# AdapterDIP8M16.net
KiCad netlist of a schematic drawn in EAGLE
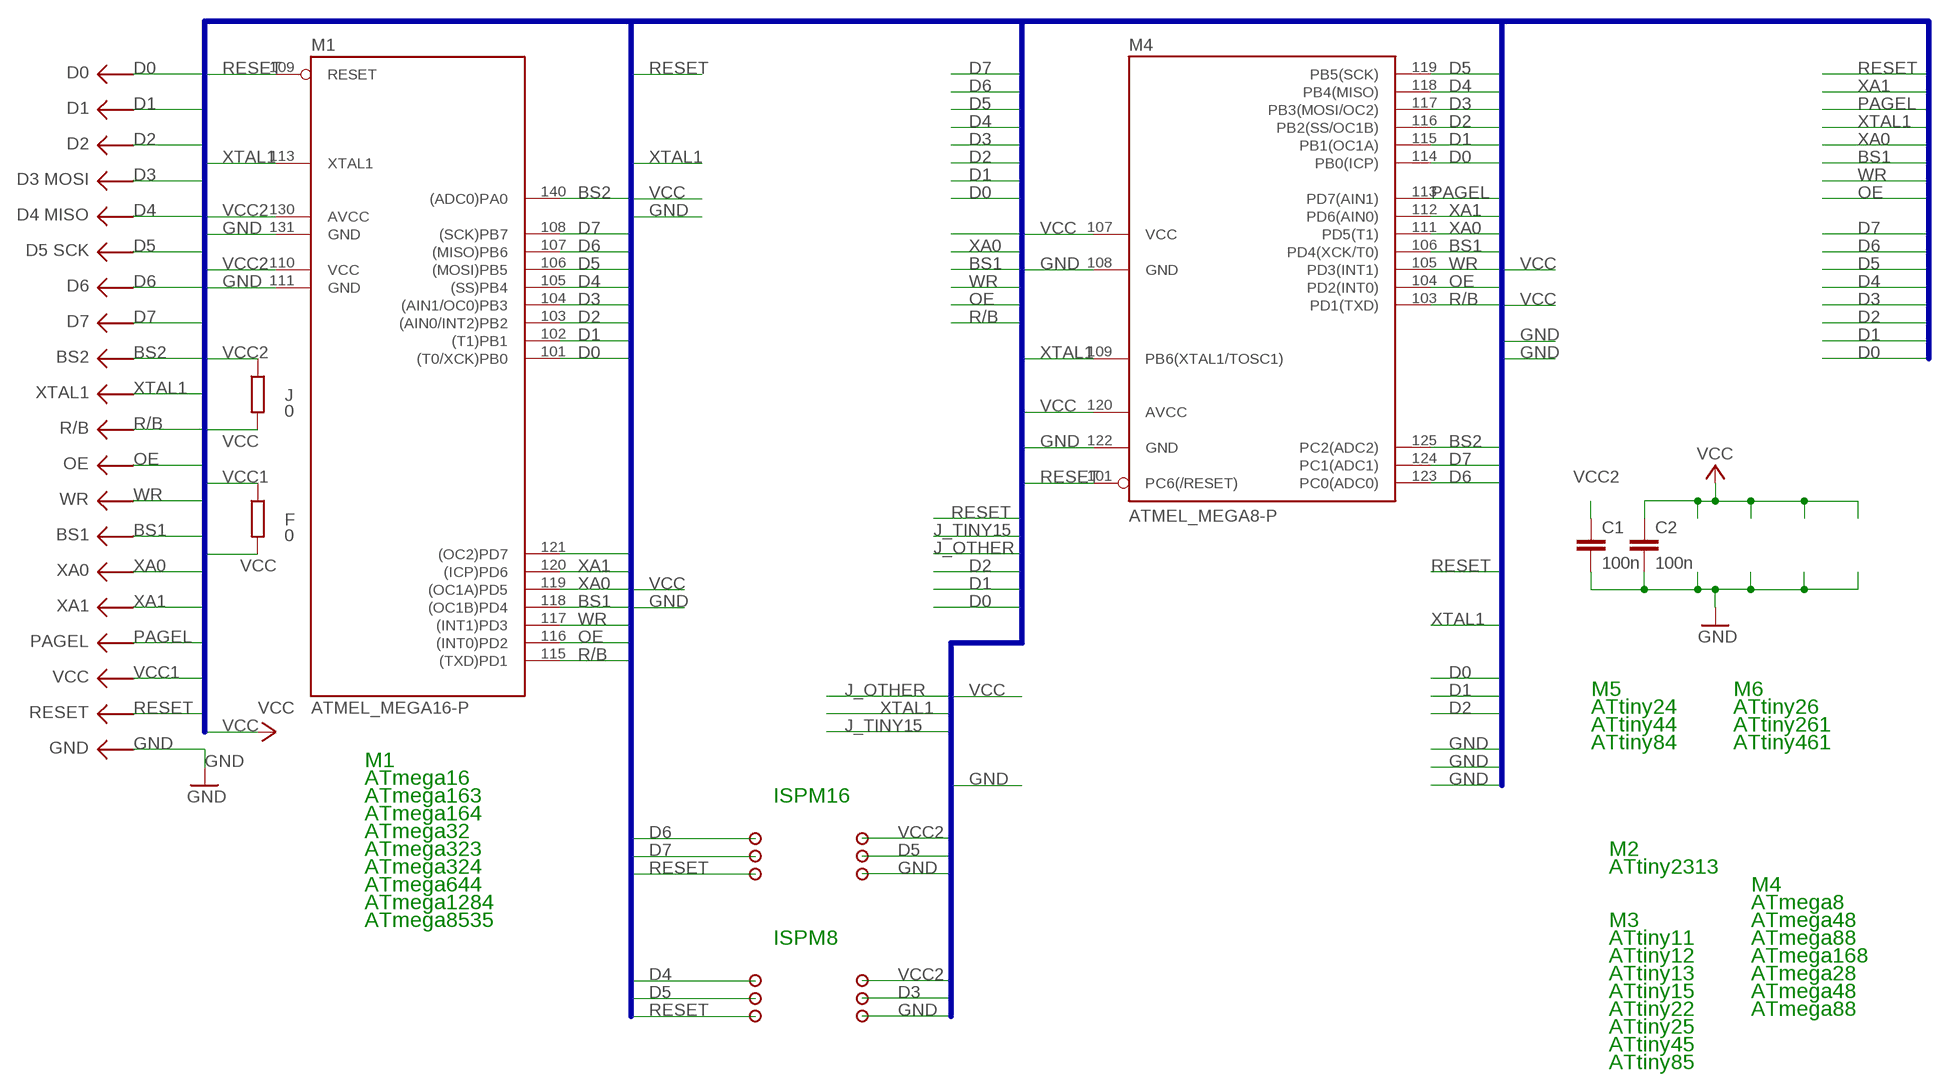
[diagram p0: schematic, sheet 1]

(export (version "E")
  (design (tool "Eeschema 10.0.6"))
  (components
    (comp (ref "C1")
      (value "100n")
      (footprint "eagle-import:RCL_C0805")
      (libsource (lib "eagle-import") (part "RCL_C-EUC0805"))
    )
    (comp (ref "C2")
      (value "100n")
      (footprint "eagle-import:RCL_C0805")
      (libsource (lib "eagle-import") (part "RCL_C-EUC0805"))
    )
    (comp (ref "F")
      (value "0")
      (footprint "eagle-import:RCL_M0805")
      (libsource (lib "eagle-import") (part "RCL_R-EU_M0805"))
    )
    (comp (ref "J")
      (value "0")
      (footprint "eagle-import:RCL_M1206")
      (libsource (lib "eagle-import") (part "RCL_R-EU_M1206"))
    )
    (comp (ref "M1")
      (value "ATMEL_MEGA16-P")
      (footprint "eagle-import:ATMEL_DIL40")
      (libsource (lib "eagle-import") (part "ATMEL_MEGA16-P"))
    )
    (comp (ref "M4")
      (value "ATMEL_MEGA8-P")
      (footprint "eagle-import:ATMEL_DIL28-3")
      (libsource (lib "eagle-import") (part "ATMEL_MEGA8-P"))
    )
    (comp (ref "U$1")
      (value "PROGRAMMER_P_AVR")
      (footprint "eagle-import:PROGRAMMER_P_AVR")
      (libsource (lib "eagle-import") (part "PROGRAMMER_P_AVR"))
    )
    (comp (ref "U$2")
      (value "PIN")
      (footprint "eagle-import:PIN")
      (libsource (lib "eagle-import") (part "PIN"))
    )
    (comp (ref "U$3")
      (value "PIN")
      (footprint "eagle-import:PIN")
      (libsource (lib "eagle-import") (part "PIN"))
    )
    (comp (ref "U$4")
      (value "PIN")
      (footprint "eagle-import:PIN")
      (libsource (lib "eagle-import") (part "PIN"))
    )
    (comp (ref "U$5")
      (value "PIN")
      (footprint "eagle-import:PIN")
      (libsource (lib "eagle-import") (part "PIN"))
    )
    (comp (ref "U$6")
      (value "PIN")
      (footprint "eagle-import:PIN")
      (libsource (lib "eagle-import") (part "PIN"))
    )
    (comp (ref "U$7")
      (value "PIN")
      (footprint "eagle-import:PIN")
      (libsource (lib "eagle-import") (part "PIN"))
    )
    (comp (ref "U$8")
      (value "PIN")
      (footprint "eagle-import:PIN")
      (libsource (lib "eagle-import") (part "PIN"))
    )
    (comp (ref "U$9")
      (value "PIN")
      (footprint "eagle-import:PIN")
      (libsource (lib "eagle-import") (part "PIN"))
    )
    (comp (ref "U$10")
      (value "PIN")
      (footprint "eagle-import:PIN")
      (libsource (lib "eagle-import") (part "PIN"))
    )
    (comp (ref "U$11")
      (value "PIN")
      (footprint "eagle-import:PIN")
      (libsource (lib "eagle-import") (part "PIN"))
    )
    (comp (ref "U$12")
      (value "PIN")
      (footprint "eagle-import:PIN")
      (libsource (lib "eagle-import") (part "PIN"))
    )
    (comp (ref "U$13")
      (value "PIN")
      (footprint "eagle-import:PIN")
      (libsource (lib "eagle-import") (part "PIN"))
    )
  )
  (nets
    (net (code "1") (name "/BS1") (class "Default")
      (node (ref "M1") (pin "118") (pinfunction "(OC1B)PD4_118") (pintype "bidirectional"))
      (node (ref "M4") (pin "106") (pinfunction "PD4(XCK/T0)_106") (pintype "bidirectional"))
      (node (ref "U$1") (pin "BS1") (pinfunction "BS1_BS1") (pintype "bidirectional"))
    )
    (net (code "2") (name "/BS2") (class "Default")
      (node (ref "M1") (pin "140") (pinfunction "(ADC0)PA0_140") (pintype "bidirectional"))
      (node (ref "M4") (pin "125") (pinfunction "PC2(ADC2)_125") (pintype "bidirectional"))
      (node (ref "U$1") (pin "BS2") (pinfunction "BS2_BS2") (pintype "bidirectional"))
    )
    (net (code "3") (name "/D0") (class "Default")
      (node (ref "M1") (pin "101") (pinfunction "(T0/XCK)PB0_101") (pintype "bidirectional"))
      (node (ref "M4") (pin "114") (pinfunction "PB0(ICP)_114") (pintype "bidirectional"))
      (node (ref "U$1") (pin "D0") (pinfunction "D0_D0") (pintype "bidirectional"))
    )
    (net (code "4") (name "/D1") (class "Default")
      (node (ref "M1") (pin "102") (pinfunction "(T1)PB1_102") (pintype "bidirectional"))
      (node (ref "M4") (pin "115") (pinfunction "PB1(OC1A)_115") (pintype "bidirectional"))
      (node (ref "U$1") (pin "D1") (pinfunction "D1_D1") (pintype "bidirectional"))
    )
    (net (code "5") (name "/D2") (class "Default")
      (node (ref "M1") (pin "103") (pinfunction "(AIN0/INT2)PB2_103") (pintype "bidirectional"))
      (node (ref "M4") (pin "116") (pinfunction "PB2(SS/OC1B)_116") (pintype "bidirectional"))
      (node (ref "U$1") (pin "D2") (pinfunction "D2_D2") (pintype "bidirectional"))
    )
    (net (code "6") (name "/D3") (class "Default")
      (node (ref "M1") (pin "104") (pinfunction "(AIN1/OC0)PB3_104") (pintype "bidirectional"))
      (node (ref "M4") (pin "117") (pinfunction "PB3(MOSI/OC2)_117") (pintype "bidirectional"))
      (node (ref "U$1") (pin "D3") (pinfunction "D3_D3") (pintype "bidirectional"))
      (node (ref "U$12") (pin "P$1") (pinfunction "1_P$1") (pintype "bidirectional"))
    )
    (net (code "7") (name "/D4") (class "Default")
      (node (ref "M1") (pin "105") (pinfunction "(SS)PB4_105") (pintype "bidirectional"))
      (node (ref "M4") (pin "118") (pinfunction "PB4(MISO)_118") (pintype "bidirectional"))
      (node (ref "U$1") (pin "D4") (pinfunction "D4_D4") (pintype "bidirectional"))
      (node (ref "U$8") (pin "P$1") (pinfunction "1_P$1") (pintype "bidirectional"))
    )
    (net (code "8") (name "/D5") (class "Default")
      (node (ref "M1") (pin "106") (pinfunction "(MOSI)PB5_106") (pintype "bidirectional"))
      (node (ref "M4") (pin "119") (pinfunction "PB5(SCK)_119") (pintype "bidirectional"))
      (node (ref "U$1") (pin "D5") (pinfunction "D5_D5") (pintype "bidirectional"))
      (node (ref "U$3") (pin "P$1") (pinfunction "1_P$1") (pintype "bidirectional"))
      (node (ref "U$9") (pin "P$1") (pinfunction "1_P$1") (pintype "bidirectional"))
    )
    (net (code "9") (name "/D6") (class "Default")
      (node (ref "M1") (pin "107") (pinfunction "(MISO)PB6_107") (pintype "bidirectional"))
      (node (ref "M4") (pin "123") (pinfunction "PC0(ADC0)_123") (pintype "bidirectional"))
      (node (ref "U$1") (pin "D6") (pinfunction "D6_D6") (pintype "bidirectional"))
      (node (ref "U$5") (pin "P$1") (pinfunction "1_P$1") (pintype "bidirectional"))
    )
    (net (code "10") (name "/D7") (class "Default")
      (node (ref "M1") (pin "108") (pinfunction "(SCK)PB7_108") (pintype "bidirectional"))
      (node (ref "M4") (pin "124") (pinfunction "PC1(ADC1)_124") (pintype "bidirectional"))
      (node (ref "U$1") (pin "D7") (pinfunction "D7_D7") (pintype "bidirectional"))
      (node (ref "U$6") (pin "P$1") (pinfunction "1_P$1") (pintype "bidirectional"))
    )
    (net (code "13") (name "/OE") (class "Default")
      (node (ref "M1") (pin "116") (pinfunction "(INT0)PD2_116") (pintype "bidirectional"))
      (node (ref "M4") (pin "104") (pinfunction "PD2(INT0)_104") (pintype "bidirectional"))
      (node (ref "U$1") (pin "OE") (pinfunction "OE_OE") (pintype "bidirectional"))
    )
    (net (code "14") (name "/PAGEL") (class "Default")
      (node (ref "M1") (pin "121") (pinfunction "(OC2)PD7_121") (pintype "bidirectional"))
      (node (ref "M4") (pin "113") (pinfunction "PD7(AIN1)_113") (pintype "bidirectional"))
      (node (ref "U$1") (pin "PAGEL") (pinfunction "PAGEL_PAGEL") (pintype "bidirectional"))
    )
    (net (code "15") (name "/RESET") (class "Default")
      (node (ref "M1") (pin "109") (pinfunction "RESET_109") (pintype "input"))
      (node (ref "M4") (pin "101") (pinfunction "PC6(/RESET)_101") (pintype "bidirectional"))
      (node (ref "U$1") (pin "RESET") (pinfunction "RESET_RESET") (pintype "bidirectional"))
      (node (ref "U$10") (pin "P$1") (pinfunction "1_P$1") (pintype "bidirectional"))
      (node (ref "U$7") (pin "P$1") (pinfunction "1_P$1") (pintype "bidirectional"))
    )
    (net (code "16") (name "/R{slash}B") (class "Default")
      (node (ref "M1") (pin "115") (pinfunction "(TXD)PD1_115") (pintype "bidirectional"))
      (node (ref "M4") (pin "103") (pinfunction "PD1(TXD)_103") (pintype "bidirectional"))
      (node (ref "U$1") (pin "RB") (pinfunction "RB_RB") (pintype "bidirectional"))
    )
    (net (code "17") (name "/VCC1") (class "Default")
      (node (ref "F") (pin "1") (pinfunction "1_1") (pintype "passive"))
      (node (ref "U$1") (pin "VCC") (pinfunction "VCC_VCC") (pintype "bidirectional"))
    )
    (net (code "18") (name "/VCC2") (class "Default")
      (node (ref "C1") (pin "1") (pinfunction "1_1") (pintype "passive"))
      (node (ref "J") (pin "1") (pinfunction "1_1") (pintype "passive"))
      (node (ref "M1") (pin "110") (pinfunction "VCC_110") (pintype "power_in"))
      (node (ref "M1") (pin "130") (pinfunction "AVCC_130") (pintype "power_in"))
      (node (ref "U$13") (pin "P$1") (pinfunction "1_P$1") (pintype "bidirectional"))
      (node (ref "U$2") (pin "P$1") (pinfunction "1_P$1") (pintype "bidirectional"))
    )
    (net (code "19") (name "/WR") (class "Default")
      (node (ref "M1") (pin "117") (pinfunction "(INT1)PD3_117") (pintype "bidirectional"))
      (node (ref "M4") (pin "105") (pinfunction "PD3(INT1)_105") (pintype "bidirectional"))
      (node (ref "U$1") (pin "WR") (pinfunction "WR_WR") (pintype "bidirectional"))
    )
    (net (code "20") (name "/XA0") (class "Default")
      (node (ref "M1") (pin "119") (pinfunction "(OC1A)PD5_119") (pintype "bidirectional"))
      (node (ref "M4") (pin "111") (pinfunction "PD5(T1)_111") (pintype "bidirectional"))
      (node (ref "U$1") (pin "XA0") (pinfunction "XA0_XA0") (pintype "bidirectional"))
    )
    (net (code "21") (name "/XA1") (class "Default")
      (node (ref "M1") (pin "120") (pinfunction "(ICP)PD6_120") (pintype "bidirectional"))
      (node (ref "M4") (pin "112") (pinfunction "PD6(AIN0)_112") (pintype "bidirectional"))
      (node (ref "U$1") (pin "XA1") (pinfunction "XA1_XA1") (pintype "bidirectional"))
    )
    (net (code "22") (name "/XTAL1") (class "Default")
      (node (ref "M1") (pin "113") (pinfunction "XTAL1_113") (pintype "bidirectional"))
      (node (ref "M4") (pin "109") (pinfunction "PB6(XTAL1/TOSC1)_109") (pintype "bidirectional"))
      (node (ref "U$1") (pin "XTAL1") (pinfunction "XTAL1_XTAL1") (pintype "bidirectional"))
    )
    (net (code "23") (name "GND") (class "Default")
      (node (ref "C1") (pin "2") (pinfunction "2_2") (pintype "passive"))
      (node (ref "C2") (pin "2") (pinfunction "2_2") (pintype "passive"))
      (node (ref "M1") (pin "111") (pinfunction "GND_111") (pintype "power_in"))
      (node (ref "M1") (pin "131") (pinfunction "GND_131") (pintype "power_in"))
      (node (ref "M4") (pin "108") (pinfunction "GND_108") (pintype "power_in"))
      (node (ref "M4") (pin "122") (pinfunction "GND_122") (pintype "power_in"))
      (node (ref "U$1") (pin "GND") (pinfunction "GND_GND") (pintype "bidirectional"))
      (node (ref "U$1") (pin "GND01") (pinfunction "GND_GND01") (pintype "bidirectional"))
      (node (ref "U$1") (pin "GND03") (pinfunction "GND_GND03") (pintype "bidirectional"))
      (node (ref "U$1") (pin "GND04") (pinfunction "GND_GND04") (pintype "bidirectional"))
      (node (ref "U$1") (pin "GND05") (pinfunction "GND_GND05") (pintype "bidirectional"))
      (node (ref "U$1") (pin "GND06") (pinfunction "GND_GND06") (pintype "bidirectional"))
      (node (ref "U$1") (pin "GND07") (pinfunction "GND_GND07") (pintype "bidirectional"))
      (node (ref "U$1") (pin "GND08") (pinfunction "GND_GND08") (pintype "bidirectional"))
      (node (ref "U$1") (pin "GND09") (pinfunction "GND_GND09") (pintype "bidirectional"))
      (node (ref "U$1") (pin "GND10") (pinfunction "GND_GND10") (pintype "bidirectional"))
      (node (ref "U$1") (pin "GND11") (pinfunction "GND_GND11") (pintype "bidirectional"))
      (node (ref "U$1") (pin "GND12") (pinfunction "GND_GND12") (pintype "bidirectional"))
      (node (ref "U$1") (pin "GND13") (pinfunction "GND_GND13") (pintype "bidirectional"))
      (node (ref "U$1") (pin "GND14") (pinfunction "GND_GND14") (pintype "bidirectional"))
      (node (ref "U$1") (pin "GND15") (pinfunction "GND_GND15") (pintype "bidirectional"))
      (node (ref "U$1") (pin "GND16") (pinfunction "GND_GND16") (pintype "bidirectional"))
      (node (ref "U$1") (pin "GND17") (pinfunction "GND_GND17") (pintype "bidirectional"))
      (node (ref "U$1") (pin "GND18") (pinfunction "GND_GND18") (pintype "bidirectional"))
      (node (ref "U$1") (pin "GND19") (pinfunction "GND_GND19") (pintype "bidirectional"))
      (node (ref "U$1") (pin "GND2") (pinfunction "GND_GND2") (pintype "bidirectional"))
      (node (ref "U$1") (pin "GND20") (pinfunction "GND_GND20") (pintype "bidirectional"))
      (node (ref "U$1") (pin "GND21") (pinfunction "GND_GND21") (pintype "bidirectional"))
      (node (ref "U$1") (pin "GND22") (pinfunction "GND_GND22") (pintype "bidirectional"))
      (node (ref "U$11") (pin "P$1") (pinfunction "1_P$1") (pintype "bidirectional"))
      (node (ref "U$4") (pin "P$1") (pinfunction "1_P$1") (pintype "bidirectional"))
    )
    (net (code "24") (name "VCC") (class "Default")
      (node (ref "C2") (pin "1") (pinfunction "1_1") (pintype "passive"))
      (node (ref "F") (pin "2") (pinfunction "2_2") (pintype "passive"))
      (node (ref "J") (pin "2") (pinfunction "2_2") (pintype "passive"))
      (node (ref "M4") (pin "107") (pinfunction "VCC_107") (pintype "power_in"))
      (node (ref "M4") (pin "120") (pinfunction "AVCC_120") (pintype "power_in"))
    )
  )
)
